# Buttons.net
KiCad netlist of a schematic drawn in Altium Designer
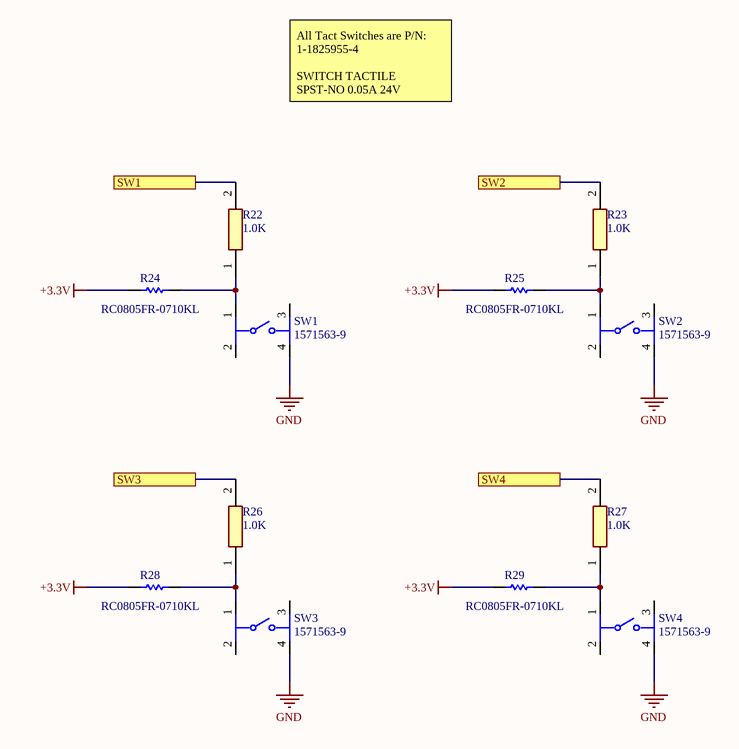
[diagram p0: Buttons.SchDoc]

(export (version "E")
  (design (tool "Eeschema 10.0.6"))
  (components
    (comp (ref "R22")
      (value "1.0K")
      (footprint "SamacSys:RESC2012X60N")
      (description "Resistor")
      (fields
        (field (name "MANUFACTURER_PART_NUMBER") "RC0805JR-071KL")
        (field (name "MOUSER PART NUMBER") "603-RC0805JR-071KL")
      )
      (libsource (lib "*") (part "RC0805JR-071KL"))
    )
    (comp (ref "R23")
      (value "1.0K")
      (footprint "SamacSys:RESC2012X60N")
      (description "Resistor")
      (fields
        (field (name "MANUFACTURER_PART_NUMBER") "RC0805JR-071KL")
        (field (name "MOUSER PART NUMBER") "603-RC0805JR-071KL")
      )
      (libsource (lib "*") (part "RC0805JR-071KL"))
    )
    (comp (ref "R24")
      (value "RC0805FR-0710KL")
      (footprint "RESC2013X60X35NL10T20")
      (description "Chip Resistor, 10 KOhm, +/- 1%, 0.125 W, -55 to 155 degC, 0805 (2012 Metric), RoHS, Tape and Reel")
      (fields (field (name "MANUFACTURER") "Yageo"))
      (libsource (lib "Altium Content Vault") (part "RES-2"))
    )
    (comp (ref "R25")
      (value "RC0805FR-0710KL")
      (footprint "RESC2013X60X35NL10T20")
      (description "Chip Resistor, 10 KOhm, +/- 1%, 0.125 W, -55 to 155 degC, 0805 (2012 Metric), RoHS, Tape and Reel")
      (fields (field (name "MANUFACTURER") "Yageo"))
      (libsource (lib "Altium Content Vault") (part "RES-2"))
    )
    (comp (ref "R26")
      (value "1.0K")
      (footprint "SamacSys:RESC2012X60N")
      (description "Resistor")
      (fields
        (field (name "MANUFACTURER_PART_NUMBER") "RC0805JR-071KL")
        (field (name "MOUSER PART NUMBER") "603-RC0805JR-071KL")
      )
      (libsource (lib "*") (part "RC0805JR-071KL"))
    )
    (comp (ref "R27")
      (value "1.0K")
      (footprint "SamacSys:RESC2012X60N")
      (description "Resistor")
      (fields
        (field (name "MANUFACTURER_PART_NUMBER") "RC0805JR-071KL")
        (field (name "MOUSER PART NUMBER") "603-RC0805JR-071KL")
      )
      (libsource (lib "*") (part "RC0805JR-071KL"))
    )
    (comp (ref "R28")
      (value "RC0805FR-0710KL")
      (footprint "RESC2013X60X35NL10T20")
      (description "Chip Resistor, 10 KOhm, +/- 1%, 0.125 W, -55 to 155 degC, 0805 (2012 Metric), RoHS, Tape and Reel")
      (fields (field (name "MANUFACTURER") "Yageo"))
      (libsource (lib "Altium Content Vault") (part "RES-2"))
    )
    (comp (ref "R29")
      (value "RC0805FR-0710KL")
      (footprint "RESC2013X60X35NL10T20")
      (description "Chip Resistor, 10 KOhm, +/- 1%, 0.125 W, -55 to 155 degC, 0805 (2012 Metric), RoHS, Tape and Reel")
      (fields (field (name "MANUFACTURER") "Yageo"))
      (libsource (lib "Altium Content Vault") (part "RES-2"))
    )
    (comp (ref "SW1")
      (value "1571563-9")
      (footprint "FP-1571563-9-MFG")
      (description "SWITCH TACTILE SPST-NO 0.05A 24V")
      (fields
        (field (name "MANUFACTURER") "TE Connectivity")
        (field (name "OCTOPART") "https://octopart.com/1571563-9-te+connectivity-41253969")
      )
      (libsource (lib "Altium Content Vault") (part "b8895f3f4cefb76e1819d2863dba89b"))
    )
    (comp (ref "SW2")
      (value "1571563-9")
      (footprint "FP-1571563-9-MFG")
      (description "SWITCH TACTILE SPST-NO 0.05A 24V")
      (fields
        (field (name "MANUFACTURER") "TE Connectivity")
        (field (name "OCTOPART") "https://octopart.com/1571563-9-te+connectivity-41253969")
      )
      (libsource (lib "Altium Content Vault") (part "b8895f3f4cefb76e1819d2863dba89b"))
    )
    (comp (ref "SW3")
      (value "1571563-9")
      (footprint "FP-1571563-9-MFG")
      (description "SWITCH TACTILE SPST-NO 0.05A 24V")
      (fields
        (field (name "MANUFACTURER") "TE Connectivity")
        (field (name "OCTOPART") "https://octopart.com/1571563-9-te+connectivity-41253969")
      )
      (libsource (lib "Altium Content Vault") (part "b8895f3f4cefb76e1819d2863dba89b"))
    )
    (comp (ref "SW4")
      (value "1571563-9")
      (footprint "FP-1571563-9-MFG")
      (description "SWITCH TACTILE SPST-NO 0.05A 24V")
      (fields
        (field (name "MANUFACTURER") "TE Connectivity")
        (field (name "OCTOPART") "https://octopart.com/1571563-9-te+connectivity-41253969")
      )
      (libsource (lib "Altium Content Vault") (part "b8895f3f4cefb76e1819d2863dba89b"))
    )
  )
  (nets
    (net (code "1") (name "+3.3V") (class "Default")
      (node (ref "R24") (pin "1") (pinfunction "1_1") (pintype "passive"))
      (node (ref "R25") (pin "1") (pinfunction "1_1") (pintype "passive"))
      (node (ref "R28") (pin "1") (pinfunction "1_1") (pintype "passive"))
      (node (ref "R29") (pin "1") (pinfunction "1_1") (pintype "passive"))
    )
    (net (code "2") (name "/SW1") (class "Default")
      (node (ref "R22") (pin "2") (pinfunction "2_2") (pintype "passive"))
    )
    (net (code "3") (name "/SW2") (class "Default")
      (node (ref "R23") (pin "2") (pinfunction "2_2") (pintype "passive"))
    )
    (net (code "4") (name "/SW3") (class "Default")
      (node (ref "R26") (pin "2") (pinfunction "2_2") (pintype "passive"))
    )
    (net (code "5") (name "/SW4") (class "Default")
      (node (ref "R27") (pin "2") (pinfunction "2_2") (pintype "passive"))
    )
    (net (code "6") (name "GND") (class "Default")
      (node (ref "SW1") (pin "4") (pinfunction "4_4") (pintype "passive"))
      (node (ref "SW2") (pin "4") (pinfunction "4_4") (pintype "passive"))
      (node (ref "SW3") (pin "4") (pinfunction "4_4") (pintype "passive"))
      (node (ref "SW4") (pin "4") (pinfunction "4_4") (pintype "passive"))
    )
    (net (code "7") (name "Net-(R22-Pad1)") (class "Default")
      (node (ref "R22") (pin "1") (pinfunction "1_1") (pintype "passive"))
      (node (ref "R24") (pin "2") (pinfunction "2_2") (pintype "passive"))
      (node (ref "SW1") (pin "1") (pinfunction "1_1") (pintype "passive"))
    )
    (net (code "8") (name "Net-(R23-Pad1)") (class "Default")
      (node (ref "R23") (pin "1") (pinfunction "1_1") (pintype "passive"))
      (node (ref "R25") (pin "2") (pinfunction "2_2") (pintype "passive"))
      (node (ref "SW2") (pin "1") (pinfunction "1_1") (pintype "passive"))
    )
    (net (code "9") (name "Net-(R26-Pad1)") (class "Default")
      (node (ref "R26") (pin "1") (pinfunction "1_1") (pintype "passive"))
      (node (ref "R28") (pin "2") (pinfunction "2_2") (pintype "passive"))
      (node (ref "SW3") (pin "1") (pinfunction "1_1") (pintype "passive"))
    )
    (net (code "10") (name "Net-(R27-Pad1)") (class "Default")
      (node (ref "R27") (pin "1") (pinfunction "1_1") (pintype "passive"))
      (node (ref "R29") (pin "2") (pinfunction "2_2") (pintype "passive"))
      (node (ref "SW4") (pin "1") (pinfunction "1_1") (pintype "passive"))
    )
    (net (code "11") (name "unconnected-(SW1-Pad2)") (class "Default")
      (node (ref "SW1") (pin "2") (pinfunction "2_2") (pintype "passive"))
    )
    (net (code "12") (name "unconnected-(SW1-Pad3)") (class "Default")
      (node (ref "SW1") (pin "3") (pinfunction "3_3") (pintype "passive"))
    )
    (net (code "13") (name "unconnected-(SW2-Pad2)") (class "Default")
      (node (ref "SW2") (pin "2") (pinfunction "2_2") (pintype "passive"))
    )
    (net (code "14") (name "unconnected-(SW2-Pad3)") (class "Default")
      (node (ref "SW2") (pin "3") (pinfunction "3_3") (pintype "passive"))
    )
    (net (code "15") (name "unconnected-(SW3-Pad2)") (class "Default")
      (node (ref "SW3") (pin "2") (pinfunction "2_2") (pintype "passive"))
    )
    (net (code "16") (name "unconnected-(SW3-Pad3)") (class "Default")
      (node (ref "SW3") (pin "3") (pinfunction "3_3") (pintype "passive"))
    )
    (net (code "17") (name "unconnected-(SW4-Pad2)") (class "Default")
      (node (ref "SW4") (pin "2") (pinfunction "2_2") (pintype "passive"))
    )
    (net (code "18") (name "unconnected-(SW4-Pad3)") (class "Default")
      (node (ref "SW4") (pin "3") (pinfunction "3_3") (pintype "passive"))
    )
  )
)
